# house_exterior_board.net
KiCad netlist of a schematic drawn in EAGLE
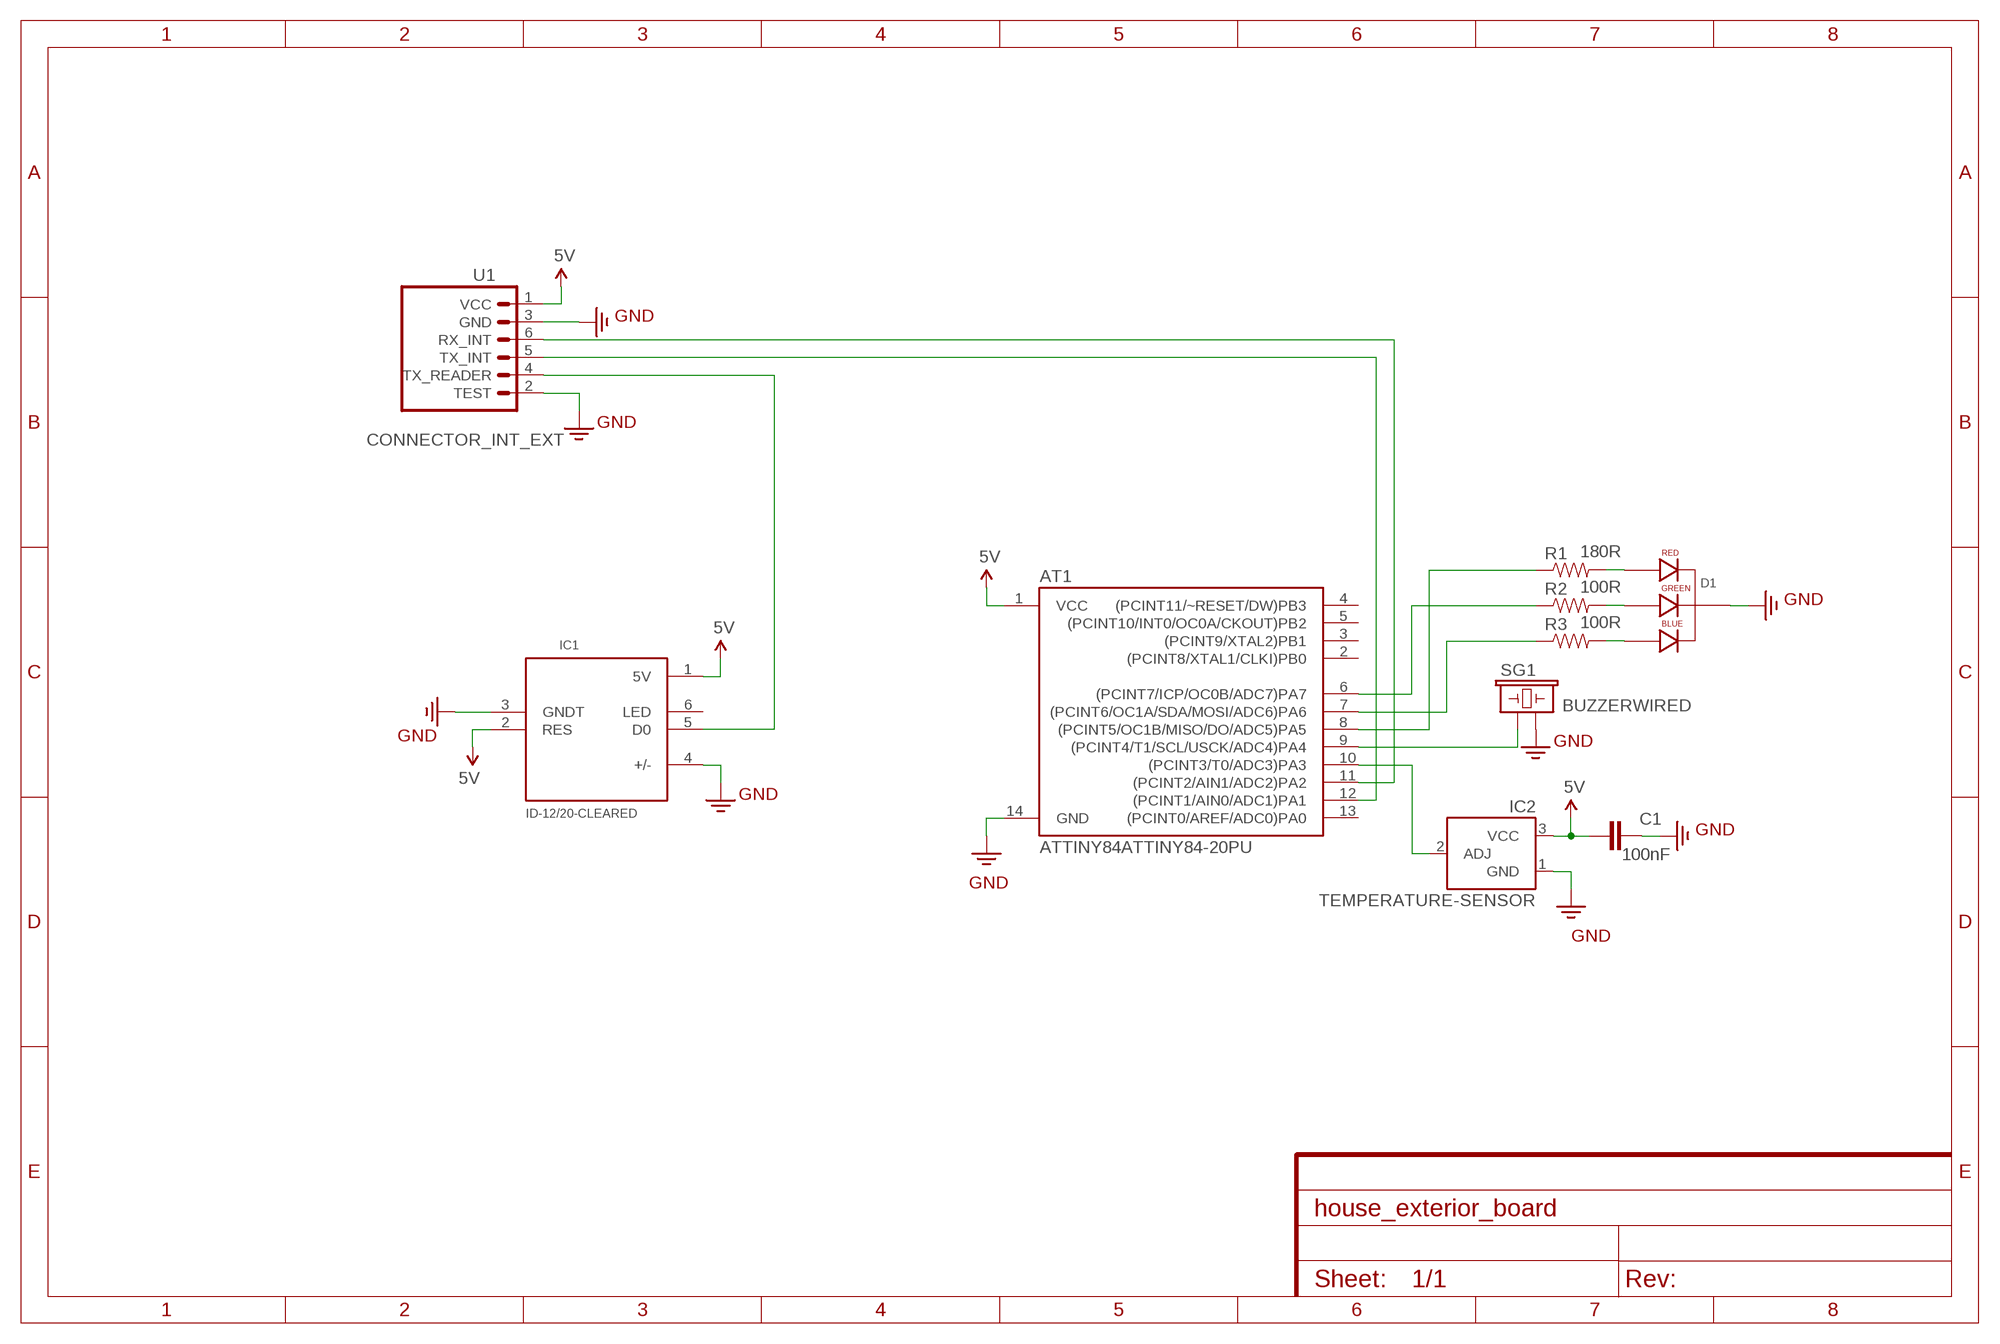
[diagram p0: schematic, sheet 1]

(export (version "E")
  (design (tool "Eeschema 10.0.6"))
  (components
    (comp (ref "AT1")
      (value "ATTINY84ATTINY84-20PU")
      (footprint "eagle-import:DIL14")
      (libsource (lib "eagle-import") (part "ATTINY84ATTINY84-20PU"))
    )
    (comp (ref "C1")
      (value "100nF")
      (footprint "eagle-import:CAP-PTH-SMALL-KIT")
      (libsource (lib "eagle-import") (part "0.1UF-50V-20%(PTH)KIT-EZ"))
    )
    (comp (ref "D1")
      (value "LED-RGB-CC-THRUCLEAR")
      (footprint "eagle-import:LED-RGB-THRU")
      (libsource (lib "eagle-import") (part "LED-RGB-CC-THRUCLEAR"))
    )
    (comp (ref "IC1")
      (value "ID-12/20-CLEARED")
      (footprint "eagle-import:1X06_COMMON")
      (libsource (lib "eagle-import") (part "ID-12/20-CLEARED"))
    )
    (comp (ref "IC2")
      (value "TEMPERATURE-SENSOR")
      (footprint "eagle-import:TO-92")
      (libsource (lib "eagle-import") (part "TEMPERATURE-SENSOR"))
    )
    (comp (ref "R1")
      (value "180R")
      (footprint "eagle-import:AXIAL-0.1")
      (libsource (lib "eagle-import") (part "RESISTORVERT"))
    )
    (comp (ref "R2")
      (value "100R")
      (footprint "eagle-import:AXIAL-0.1")
      (libsource (lib "eagle-import") (part "RESISTORVERT"))
    )
    (comp (ref "R3")
      (value "100R")
      (footprint "eagle-import:AXIAL-0.1")
      (libsource (lib "eagle-import") (part "RESISTORVERT"))
    )
    (comp (ref "SG1")
      (value "BUZZERWIRED")
      (footprint "eagle-import:1X02")
      (libsource (lib "eagle-import") (part "BUZZERWIRED"))
    )
    (comp (ref "U1")
      (value "CONNECTOR_INT_EXT")
      (footprint "eagle-import:1X06_COMMON")
      (libsource (lib "eagle-import") (part "CONNECTOR_INT_EXT"))
    )
  )
  (nets
    (net (code "1") (name "5V") (class "Default")
      (node (ref "AT1") (pin "1") (pinfunction "VCC_1") (pintype "bidirectional"))
      (node (ref "C1") (pin "1") (pinfunction "1_1") (pintype "passive"))
      (node (ref "IC1") (pin "1") (pinfunction "5V_1") (pintype "bidirectional"))
      (node (ref "IC1") (pin "2") (pinfunction "RES_2") (pintype "bidirectional"))
      (node (ref "IC2") (pin "3") (pinfunction "VCC_3") (pintype "bidirectional"))
      (node (ref "U1") (pin "1") (pinfunction "VCC_1") (pintype "passive"))
    )
    (net (code "2") (name "GND") (class "Default")
      (node (ref "AT1") (pin "14") (pinfunction "GND_14") (pintype "bidirectional"))
      (node (ref "C1") (pin "2") (pinfunction "2_2") (pintype "passive"))
      (node (ref "D1") (pin "2") (pinfunction "CATHODE_2") (pintype "bidirectional"))
      (node (ref "IC1") (pin "3") (pinfunction "GNDT_3") (pintype "bidirectional"))
      (node (ref "IC1") (pin "4") (pinfunction "+/-_4") (pintype "bidirectional"))
      (node (ref "IC2") (pin "1") (pinfunction "GND_1") (pintype "bidirectional"))
      (node (ref "SG1") (pin "2") (pinfunction "2_2") (pintype "passive"))
      (node (ref "U1") (pin "2") (pinfunction "TEST_2") (pintype "passive"))
      (node (ref "U1") (pin "3") (pinfunction "GND_3") (pintype "passive"))
    )
    (net (code "3") (name "Net-(AT1-(PCINT1{slash}AIN0{slash}ADC1)PA1)") (class "Default")
      (node (ref "AT1") (pin "12") (pinfunction "(PCINT1/AIN0/ADC1)PA1_12") (pintype "bidirectional"))
      (node (ref "U1") (pin "5") (pinfunction "TX_INT_5") (pintype "passive"))
    )
    (net (code "4") (name "Net-(AT1-(PCINT2{slash}AIN1{slash}ADC2)PA2)") (class "Default")
      (node (ref "AT1") (pin "11") (pinfunction "(PCINT2/AIN1/ADC2)PA2_11") (pintype "bidirectional"))
      (node (ref "U1") (pin "6") (pinfunction "RX_INT_6") (pintype "passive"))
    )
    (net (code "5") (name "Net-(AT1-(PCINT3{slash}T0{slash}ADC3)PA3)") (class "Default")
      (node (ref "AT1") (pin "10") (pinfunction "(PCINT3/T0/ADC3)PA3_10") (pintype "bidirectional"))
      (node (ref "IC2") (pin "2") (pinfunction "ADJ_2") (pintype "bidirectional"))
    )
    (net (code "6") (name "Net-(AT1-(PCINT4{slash}T1{slash}SCL{slash}USCK{slash}ADC4)PA4)") (class "Default")
      (node (ref "AT1") (pin "9") (pinfunction "(PCINT4/T1/SCL/USCK/ADC4)PA4_9") (pintype "bidirectional"))
      (node (ref "SG1") (pin "1") (pinfunction "1_1") (pintype "passive"))
    )
    (net (code "7") (name "Net-(AT1-(PCINT5{slash}OC1B{slash}MISO{slash}DO{slash}ADC5)PA5)") (class "Default")
      (node (ref "AT1") (pin "8") (pinfunction "(PCINT5/OC1B/MISO/DO/ADC5)PA5_8") (pintype "bidirectional"))
      (node (ref "R1") (pin "P$1") (pinfunction "1_P$1") (pintype "passive"))
    )
    (net (code "8") (name "Net-(AT1-(PCINT6{slash}OC1A{slash}SDA{slash}MOSI{slash}ADC6)PA6)") (class "Default")
      (node (ref "AT1") (pin "7") (pinfunction "(PCINT6/OC1A/SDA/MOSI/ADC6)PA6_7") (pintype "bidirectional"))
      (node (ref "R3") (pin "P$1") (pinfunction "1_P$1") (pintype "passive"))
    )
    (net (code "9") (name "Net-(AT1-(PCINT7{slash}ICP{slash}OC0B{slash}ADC7)PA7)") (class "Default")
      (node (ref "AT1") (pin "6") (pinfunction "(PCINT7/ICP/OC0B/ADC7)PA7_6") (pintype "bidirectional"))
      (node (ref "R2") (pin "P$1") (pinfunction "1_P$1") (pintype "passive"))
    )
    (net (code "10") (name "Net-(D1-BLUE_CATHODE)") (class "Default")
      (node (ref "D1") (pin "4") (pinfunction "BLUE_CATHODE_4") (pintype "bidirectional"))
      (node (ref "R3") (pin "P$2") (pinfunction "2_P$2") (pintype "passive"))
    )
    (net (code "11") (name "Net-(D1-GREEN_CATHODE)") (class "Default")
      (node (ref "D1") (pin "3") (pinfunction "GREEN_CATHODE_3") (pintype "bidirectional"))
      (node (ref "R2") (pin "P$2") (pinfunction "2_P$2") (pintype "passive"))
    )
    (net (code "12") (name "Net-(D1-RED_CATHODE)") (class "Default")
      (node (ref "D1") (pin "1") (pinfunction "RED_CATHODE_1") (pintype "bidirectional"))
      (node (ref "R1") (pin "P$2") (pinfunction "2_P$2") (pintype "passive"))
    )
    (net (code "13") (name "Net-(IC1-D0)") (class "Default")
      (node (ref "IC1") (pin "5") (pinfunction "D0_5") (pintype "bidirectional"))
      (node (ref "U1") (pin "4") (pinfunction "TX_READER_4") (pintype "passive"))
    )
    (net (code "14") (name "unconnected-(AT1-(PCINT0{slash}AREF{slash}ADC0)PA0-Pad13)") (class "Default")
      (node (ref "AT1") (pin "13") (pinfunction "(PCINT0/AREF/ADC0)PA0_13") (pintype "bidirectional"))
    )
    (net (code "15") (name "unconnected-(AT1-(PCINT8{slash}XTAL1{slash}CLKI)PB0-Pad2)") (class "Default")
      (node (ref "AT1") (pin "2") (pinfunction "(PCINT8/XTAL1/CLKI)PB0_2") (pintype "bidirectional"))
    )
    (net (code "16") (name "unconnected-(AT1-(PCINT9{slash}XTAL2)PB1-Pad3)") (class "Default")
      (node (ref "AT1") (pin "3") (pinfunction "(PCINT9/XTAL2)PB1_3") (pintype "bidirectional"))
    )
    (net (code "17") (name "unconnected-(AT1-(PCINT10{slash}INT0{slash}OC0A{slash}CKOUT)PB2-Pad5)") (class "Default")
      (node (ref "AT1") (pin "5") (pinfunction "(PCINT10/INT0/OC0A/CKOUT)PB2_5") (pintype "bidirectional"))
    )
    (net (code "18") (name "unconnected-(AT1-(PCINT11{slash}~{RESET{slash}DW})PB3-Pad4)") (class "Default")
      (node (ref "AT1") (pin "4") (pinfunction "(PCINT11/~{RESET/DW})PB3_4") (pintype "bidirectional"))
    )
    (net (code "19") (name "unconnected-(IC1-LED-Pad6)") (class "Default")
      (node (ref "IC1") (pin "6") (pinfunction "LED_6") (pintype "bidirectional"))
    )
  )
)
